# Ammeter.net
KiCad netlist of a schematic drawn in Altium Designer
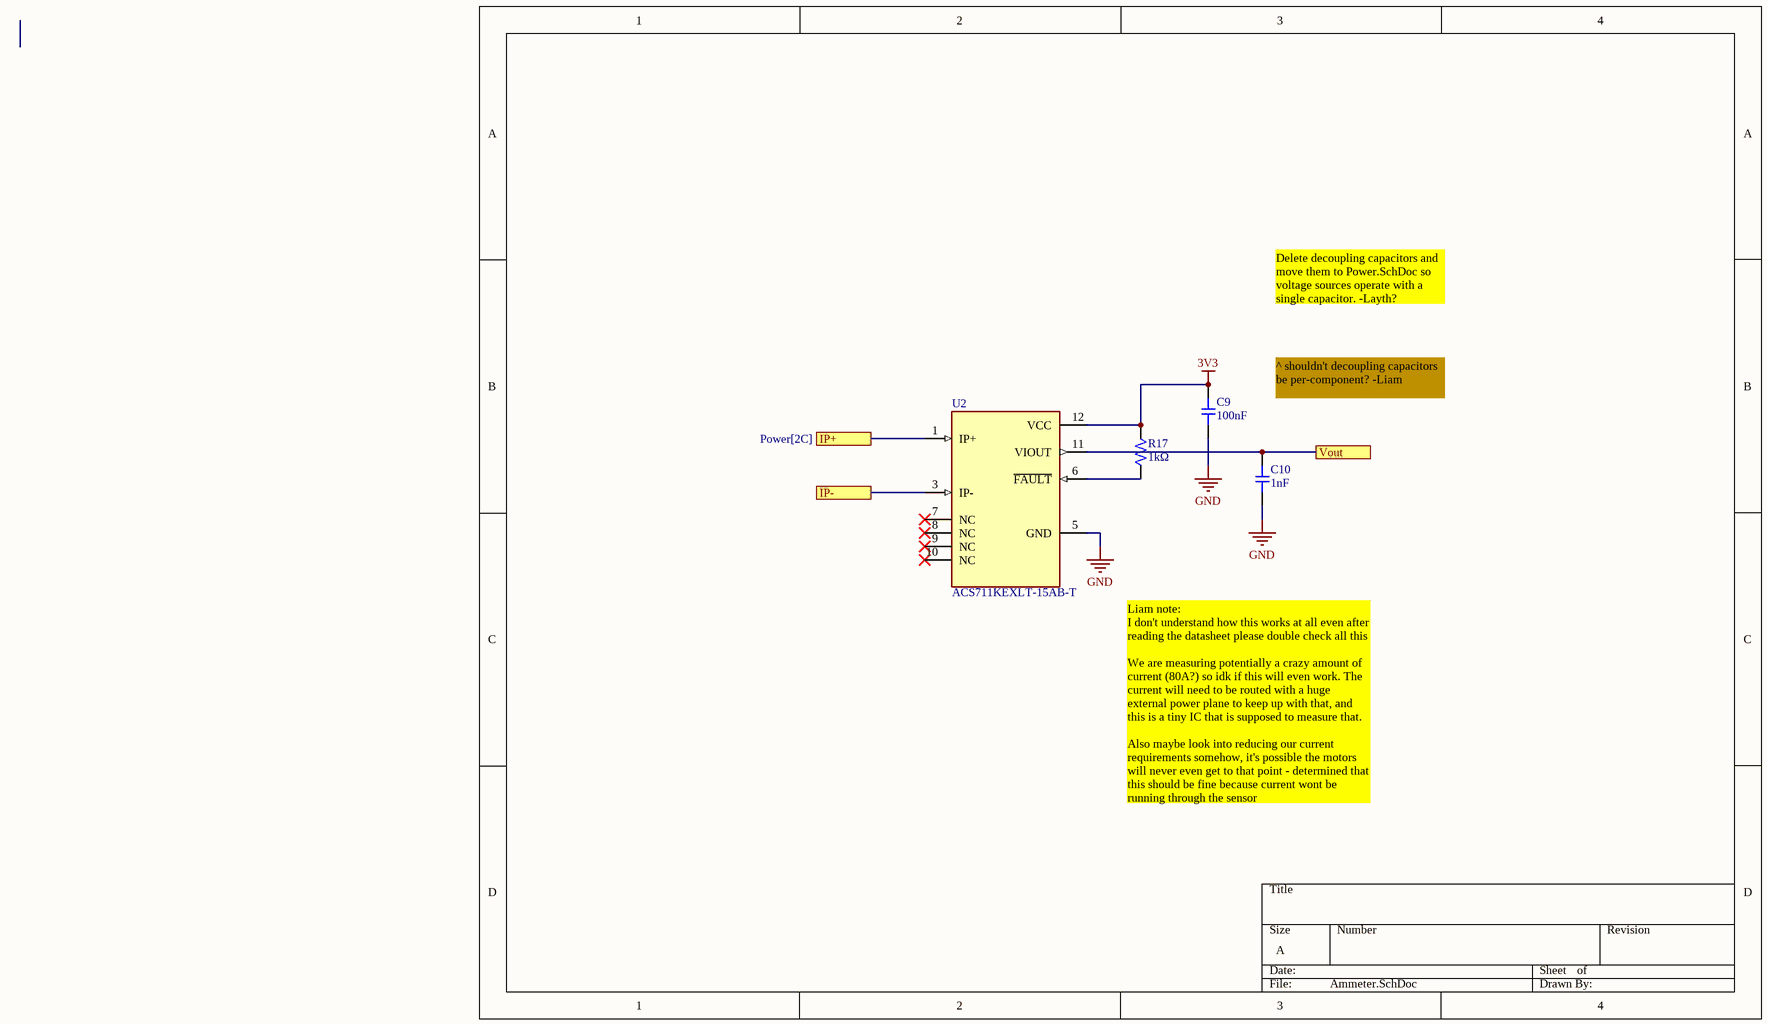
[diagram p0: Ammeter.SchDoc]

(export (version "E")
  (design (tool "Eeschema 10.0.6"))
  (components
    (comp (ref "C9")
      (value "CC0805KRX7R9BB104")
      (footprint "CAP-0805")
      (description "Capacitor, Ceramic (MLCC), 100nF, ±10%, 50V, X7R, ±10%, SMD 0805")
      (fields
        (field (name "JLCPCB BASIC PART") "Yes")
        (field (name "CAPACITANCE") "100nF")
        (field (name "JLCPCB PART NUMBER") "C49678")
      )
      (libsource (lib "jlcpcb_2024_10_capacitors_basic") (part "CC0805KRX7R9BB104"))
    )
    (comp (ref "C10")
      (value "CL21B102KBCNNNC")
      (footprint "CAP-0805")
      (description "Capacitor, Ceramic (MLCC), 1nF, ±10%, 50V, X7R, ±10%, SMD 0805")
      (fields
        (field (name "JLCPCB BASIC PART") "Yes")
        (field (name "CAPACITANCE") "1nF")
        (field (name "JLCPCB PART NUMBER") "C46653")
      )
      (libsource (lib "jlcpcb_2024_10_capacitors_basic") (part "CL21B102KBCNNNC"))
    )
    (comp (ref "R17")
      (value "~")
      (footprint "RES-0603")
      (description "Resistor, 1kΩ, ±1%, 100mW, 75V, ±100ppm/℃, -55℃~+155℃, SMD 0603")
      (fields
        (field (name "MANUFACTURER") "Uniroyal")
        (field (name "MANUFACTURER PART NUMBER") "0603WAF1001T5E")
        (field (name "RESISTANCE") "1kΩ")
      )
      (libsource (lib "jlcpcb_2024_10_resistors_basic") (part "0603WAF1001T5E"))
    )
    (comp (ref "U2")
      (value "ACS711KEXLT-15AB-T")
      (footprint "XDCR_ACS711KEXLT-15AB-T")
      (description "Current Sensor 15.5A 1 Channel Hall Effect, Open Loop Bidirectional 12-PowerWFQFN")
      (fields (field (name "MF") "Allegro MicroSystems LLC"))
      (libsource (lib "ACS711KEXLT-15AB-T") (part "ACS711KEXLT-15AB-T"))
    )
  )
  (nets
    (net (code "1") (name "/IP+") (class "Default")
      (node (ref "U2") (pin "1") (pinfunction "IP+_1") (pintype "input"))
    )
    (net (code "2") (name "/IP-") (class "Default")
      (node (ref "U2") (pin "3") (pinfunction "IP-_3") (pintype "input"))
    )
    (net (code "3") (name "/Vout") (class "Default")
      (node (ref "C10") (pin "2") (pinfunction "2_2") (pintype "passive"))
      (node (ref "U2") (pin "11") (pinfunction "VIOUT_11") (pintype "output"))
    )
    (net (code "4") (name "3V3") (class "Default")
      (node (ref "C9") (pin "2") (pinfunction "2_2") (pintype "passive"))
      (node (ref "R17") (pin "2") (pinfunction "2_2") (pintype "passive"))
      (node (ref "U2") (pin "12") (pinfunction "VCC_12") (pintype "power_in"))
    )
    (net (code "5") (name "GND") (class "Default")
      (node (ref "C10") (pin "1") (pinfunction "1_1") (pintype "passive"))
      (node (ref "C9") (pin "1") (pinfunction "1_1") (pintype "passive"))
      (node (ref "U2") (pin "5") (pinfunction "GND_5") (pintype "power_in"))
    )
    (net (code "6") (name "Net-(U2-~{FAULT})") (class "Default")
      (node (ref "R17") (pin "1") (pinfunction "1_1") (pintype "passive"))
      (node (ref "U2") (pin "6") (pinfunction "~{FAULT}_6") (pintype "input"))
    )
    (net (code "7") (name "unconnected-(U2-NC-Pad7)") (class "Default")
      (node (ref "U2") (pin "7") (pinfunction "NC_7") (pintype "passive+no_connect"))
    )
    (net (code "8") (name "unconnected-(U2-NC-Pad8)") (class "Default")
      (node (ref "U2") (pin "8") (pinfunction "NC_8") (pintype "passive+no_connect"))
    )
    (net (code "9") (name "unconnected-(U2-NC-Pad9)") (class "Default")
      (node (ref "U2") (pin "9") (pinfunction "NC_9") (pintype "passive+no_connect"))
    )
    (net (code "10") (name "unconnected-(U2-NC-Pad10)") (class "Default")
      (node (ref "U2") (pin "10") (pinfunction "NC_10") (pintype "passive+no_connect"))
    )
  )
)
